# Transmitter.net
KiCad netlist of a schematic drawn in EAGLE
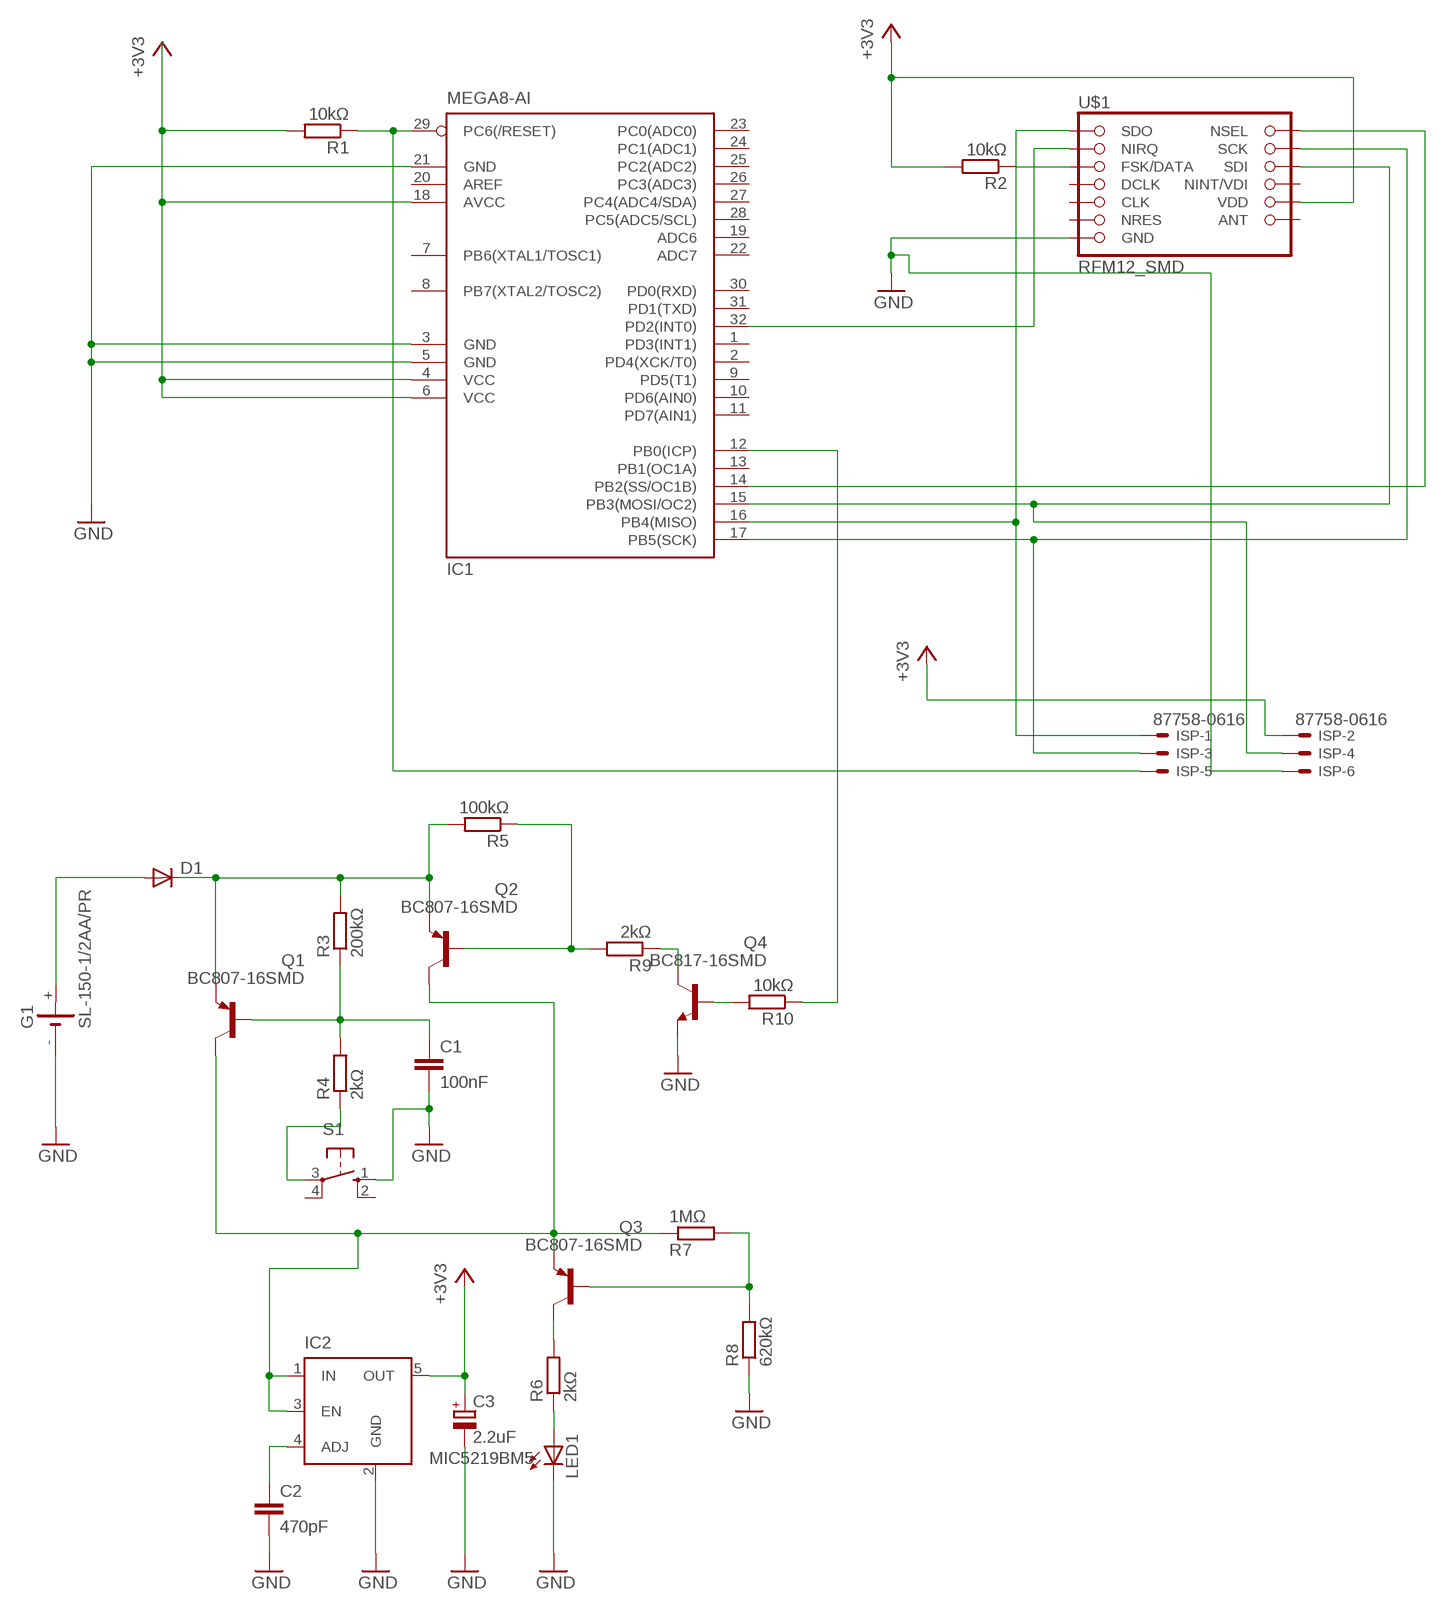
[diagram p0: schematic, sheet 1]

(export (version "E")
  (design (tool "Eeschema 10.0.6"))
  (components
    (comp (ref "C1")
      (value "100nF")
      (footprint "eagle-import:C0603")
      (libsource (lib "eagle-import") (part "C-EUC0603"))
    )
    (comp (ref "C2")
      (value "470pF")
      (footprint "eagle-import:C0603")
      (libsource (lib "eagle-import") (part "C-EUC0603"))
    )
    (comp (ref "C3")
      (value "2.2uF")
      (footprint "eagle-import:SMC_A")
      (libsource (lib "eagle-import") (part "CPOL-EUSMCA"))
    )
    (comp (ref "D1")
      (value "DIODE-SOD80C")
      (footprint "eagle-import:SOD80C")
      (libsource (lib "eagle-import") (part "DIODE-SOD80C"))
    )
    (comp (ref "G1")
      (value "SL-150-1/2AA/PR")
      (footprint "eagle-import:SL-150-1_2AA_PR")
      (libsource (lib "eagle-import") (part "SL-150-1/2AA/PR"))
    )
    (comp (ref "IC1")
      (value "MEGA8-AI")
      (footprint "eagle-import:TQFP32-08")
      (fields (field (name "MPN") "ATMEGA8-16AU"))
      (libsource (lib "eagle-import") (part "MEGA8-AI"))
    )
    (comp (ref "IC2")
      (value "MIC5219BM5")
      (footprint "eagle-import:SOT23-5")
      (fields (field (name "MF") "ALTERA CORPORATION") (field (name "MPN") "MIC5219BM5 TR"))
      (libsource (lib "eagle-import") (part "MIC5219BM5"))
    )
    (comp (ref "ISP")
      (value "87758-0616")
      (footprint "eagle-import:87758-0616")
      (libsource (lib "eagle-import") (part "87758-0616"))
    )
    (comp (ref "LED1")
      (value "LED3MM")
      (footprint "eagle-import:LED3MM")
      (libsource (lib "eagle-import") (part "LED3MM"))
    )
    (comp (ref "Q1")
      (value "BC807-16SMD")
      (footprint "eagle-import:SOT23-BEC")
      (libsource (lib "eagle-import") (part "BC807SMD-16"))
    )
    (comp (ref "Q2")
      (value "BC807-16SMD")
      (footprint "eagle-import:SOT23-BEC")
      (libsource (lib "eagle-import") (part "BC807SMD-16"))
    )
    (comp (ref "Q3")
      (value "BC807-16SMD")
      (footprint "eagle-import:SOT23-BEC")
      (libsource (lib "eagle-import") (part "BC807SMD-16"))
    )
    (comp (ref "Q4")
      (value "BC817-16SMD")
      (footprint "eagle-import:SOT23-BEC")
      (libsource (lib "eagle-import") (part "BC817SMD-16"))
    )
    (comp (ref "R1")
      (value "10kΩ")
      (footprint "eagle-import:R0603")
      (libsource (lib "eagle-import") (part "R-EU_R0603"))
    )
    (comp (ref "R2")
      (value "10kΩ")
      (footprint "eagle-import:R0603")
      (libsource (lib "eagle-import") (part "R-EU_R0603"))
    )
    (comp (ref "R3")
      (value "200kΩ")
      (footprint "eagle-import:R0603")
      (libsource (lib "eagle-import") (part "R-EU_R0603"))
    )
    (comp (ref "R4")
      (value "2kΩ")
      (footprint "eagle-import:R0603")
      (libsource (lib "eagle-import") (part "R-EU_R0603"))
    )
    (comp (ref "R5")
      (value "100kΩ")
      (footprint "eagle-import:R0603")
      (libsource (lib "eagle-import") (part "R-EU_R0603"))
    )
    (comp (ref "R6")
      (value "2kΩ")
      (footprint "eagle-import:R0603")
      (libsource (lib "eagle-import") (part "R-EU_R0603"))
    )
    (comp (ref "R7")
      (value "1MΩ")
      (footprint "eagle-import:R0603")
      (libsource (lib "eagle-import") (part "R-EU_R0603"))
    )
    (comp (ref "R8")
      (value "620kΩ")
      (footprint "eagle-import:R0603")
      (libsource (lib "eagle-import") (part "R-EU_R0603"))
    )
    (comp (ref "R9")
      (value "2kΩ")
      (footprint "eagle-import:R0603")
      (libsource (lib "eagle-import") (part "R-EU_R0603"))
    )
    (comp (ref "R10")
      (value "10kΩ")
      (footprint "eagle-import:R0603")
      (libsource (lib "eagle-import") (part "R-EU_R0603"))
    )
    (comp (ref "S1")
      (value "10-XX")
      (footprint "eagle-import:B3F-10XX")
      (fields (field (name "MPN") "B3F-1000"))
      (libsource (lib "eagle-import") (part "10-XX"))
    )
    (comp (ref "U$1")
      (value "RFM12_SMD")
      (footprint "eagle-import:RFM12_SMD")
      (libsource (lib "eagle-import") (part "RFM12_SMD"))
    )
  )
  (nets
    (net (code "1") (name "+3V3") (class "Default")
      (node (ref "C3") (pin "+") (pinfunction "+_+") (pintype "passive"))
      (node (ref "IC1") (pin "18") (pinfunction "AVCC_18") (pintype "power_in"))
      (node (ref "IC1") (pin "4") (pinfunction "VCC_4") (pintype "power_in"))
      (node (ref "IC1") (pin "6") (pinfunction "VCC_6") (pintype "power_in"))
      (node (ref "IC2") (pin "5") (pinfunction "OUT_5") (pintype "output"))
      (node (ref "ISP") (pin "2") (pinfunction "S_2") (pintype "passive"))
      (node (ref "R1") (pin "2") (pinfunction "2_2") (pintype "passive"))
      (node (ref "R2") (pin "2") (pinfunction "2_2") (pintype "passive"))
      (node (ref "U$1") (pin "9") (pinfunction "VDD_9") (pintype "power_in"))
    )
    (net (code "2") (name "GND") (class "Default")
      (node (ref "C1") (pin "2") (pinfunction "2_2") (pintype "passive"))
      (node (ref "C2") (pin "2") (pinfunction "2_2") (pintype "passive"))
      (node (ref "C3") (pin "-") (pinfunction "-_-") (pintype "passive"))
      (node (ref "G1") (pin "-") (pinfunction "-_-") (pintype "passive"))
      (node (ref "IC1") (pin "21") (pinfunction "GND_21") (pintype "power_in"))
      (node (ref "IC1") (pin "3") (pinfunction "GND_3") (pintype "power_in"))
      (node (ref "IC1") (pin "5") (pinfunction "GND_5") (pintype "power_in"))
      (node (ref "IC2") (pin "2") (pinfunction "GND_2") (pintype "power_in"))
      (node (ref "ISP") (pin "6") (pinfunction "S_6") (pintype "passive"))
      (node (ref "LED1") (pin "K") (pinfunction "C_K") (pintype "passive"))
      (node (ref "Q4") (pin "E") (pinfunction "E_E") (pintype "passive"))
      (node (ref "R8") (pin "1") (pinfunction "1_1") (pintype "passive"))
      (node (ref "S1") (pin "1") (pinfunction "S_1") (pintype "passive"))
      (node (ref "U$1") (pin "10") (pinfunction "GND_10") (pintype "power_in"))
      (node (ref "U$1") (pin "7") (pinfunction "GND_7") (pintype "power_in"))
    )
    (net (code "3") (name "Net-(C1-Pad1)") (class "Default")
      (node (ref "C1") (pin "1") (pinfunction "1_1") (pintype "passive"))
      (node (ref "Q1") (pin "B") (pinfunction "B_B") (pintype "passive"))
      (node (ref "R3") (pin "1") (pinfunction "1_1") (pintype "passive"))
      (node (ref "R4") (pin "2") (pinfunction "2_2") (pintype "passive"))
    )
    (net (code "4") (name "Net-(D1-PadA)") (class "Default")
      (node (ref "D1") (pin "A") (pinfunction "A_A") (pintype "passive"))
      (node (ref "G1") (pin "+") (pinfunction "+_+") (pintype "passive"))
    )
    (net (code "5") (name "Net-(D1-PadC)") (class "Default")
      (node (ref "D1") (pin "C") (pinfunction "C_C") (pintype "passive"))
      (node (ref "Q1") (pin "E") (pinfunction "E_E") (pintype "passive"))
      (node (ref "Q2") (pin "E") (pinfunction "E_E") (pintype "passive"))
      (node (ref "R3") (pin "2") (pinfunction "2_2") (pintype "passive"))
      (node (ref "R5") (pin "2") (pinfunction "2_2") (pintype "passive"))
    )
    (net (code "6") (name "Net-(IC1-PB0(ICP))") (class "Default")
      (node (ref "IC1") (pin "12") (pinfunction "PB0(ICP)_12") (pintype "bidirectional"))
      (node (ref "R10") (pin "1") (pinfunction "1_1") (pintype "passive"))
    )
    (net (code "7") (name "Net-(IC1-PB2(SS{slash}OC1B))") (class "Default")
      (node (ref "IC1") (pin "14") (pinfunction "PB2(SS/OC1B)_14") (pintype "bidirectional"))
      (node (ref "U$1") (pin "14") (pinfunction "NSEL_14") (pintype "input"))
    )
    (net (code "8") (name "Net-(IC1-PB3(MOSI{slash}OC2))") (class "Default")
      (node (ref "IC1") (pin "15") (pinfunction "PB3(MOSI/OC2)_15") (pintype "bidirectional"))
      (node (ref "ISP") (pin "4") (pinfunction "S_4") (pintype "passive"))
      (node (ref "U$1") (pin "12") (pinfunction "SDI_12") (pintype "input"))
    )
    (net (code "9") (name "Net-(IC1-PB4(MISO))") (class "Default")
      (node (ref "IC1") (pin "16") (pinfunction "PB4(MISO)_16") (pintype "bidirectional"))
      (node (ref "ISP") (pin "1") (pinfunction "S_1") (pintype "passive"))
      (node (ref "U$1") (pin "1") (pinfunction "SDO_1") (pintype "output"))
    )
    (net (code "10") (name "Net-(IC1-PB5(SCK))") (class "Default")
      (node (ref "IC1") (pin "17") (pinfunction "PB5(SCK)_17") (pintype "bidirectional"))
      (node (ref "ISP") (pin "3") (pinfunction "S_3") (pintype "passive"))
      (node (ref "U$1") (pin "13") (pinfunction "SCK_13") (pintype "input"))
    )
    (net (code "11") (name "Net-(IC1-PC6({slash}RESET))") (class "Default")
      (node (ref "IC1") (pin "29") (pinfunction "PC6(/RESET)_29") (pintype "bidirectional"))
      (node (ref "ISP") (pin "5") (pinfunction "S_5") (pintype "passive"))
      (node (ref "R1") (pin "1") (pinfunction "1_1") (pintype "passive"))
    )
    (net (code "12") (name "Net-(IC1-PD2(INT0))") (class "Default")
      (node (ref "IC1") (pin "32") (pinfunction "PD2(INT0)_32") (pintype "bidirectional"))
      (node (ref "U$1") (pin "2") (pinfunction "NIRQ_2") (pintype "output"))
    )
    (net (code "13") (name "Net-(IC2-ADJ)") (class "Default")
      (node (ref "C2") (pin "1") (pinfunction "1_1") (pintype "passive"))
      (node (ref "IC2") (pin "4") (pinfunction "ADJ_4") (pintype "passive"))
    )
    (net (code "14") (name "Net-(IC2-EN)") (class "Default")
      (node (ref "IC2") (pin "1") (pinfunction "IN_1") (pintype "input"))
      (node (ref "IC2") (pin "3") (pinfunction "EN_3") (pintype "input"))
      (node (ref "Q1") (pin "C") (pinfunction "C_C") (pintype "passive"))
      (node (ref "Q2") (pin "C") (pinfunction "C_C") (pintype "passive"))
      (node (ref "Q3") (pin "E") (pinfunction "E_E") (pintype "passive"))
      (node (ref "R7") (pin "1") (pinfunction "1_1") (pintype "passive"))
    )
    (net (code "15") (name "Net-(LED1-PadA)") (class "Default")
      (node (ref "LED1") (pin "A") (pinfunction "A_A") (pintype "passive"))
      (node (ref "R6") (pin "1") (pinfunction "1_1") (pintype "passive"))
    )
    (net (code "16") (name "Net-(Q2-PadB)") (class "Default")
      (node (ref "Q2") (pin "B") (pinfunction "B_B") (pintype "passive"))
      (node (ref "R5") (pin "1") (pinfunction "1_1") (pintype "passive"))
      (node (ref "R9") (pin "2") (pinfunction "2_2") (pintype "passive"))
    )
    (net (code "17") (name "Net-(Q3-PadB)") (class "Default")
      (node (ref "Q3") (pin "B") (pinfunction "B_B") (pintype "passive"))
      (node (ref "R7") (pin "2") (pinfunction "2_2") (pintype "passive"))
      (node (ref "R8") (pin "2") (pinfunction "2_2") (pintype "passive"))
    )
    (net (code "18") (name "Net-(Q3-PadC)") (class "Default")
      (node (ref "Q3") (pin "C") (pinfunction "C_C") (pintype "passive"))
      (node (ref "R6") (pin "2") (pinfunction "2_2") (pintype "passive"))
    )
    (net (code "19") (name "Net-(Q4-PadB)") (class "Default")
      (node (ref "Q4") (pin "B") (pinfunction "B_B") (pintype "passive"))
      (node (ref "R10") (pin "2") (pinfunction "2_2") (pintype "passive"))
    )
    (net (code "20") (name "Net-(Q4-PadC)") (class "Default")
      (node (ref "Q4") (pin "C") (pinfunction "C_C") (pintype "passive"))
      (node (ref "R9") (pin "1") (pinfunction "1_1") (pintype "passive"))
    )
    (net (code "21") (name "Net-(S1-P)") (class "Default")
      (node (ref "R4") (pin "1") (pinfunction "1_1") (pintype "passive"))
      (node (ref "S1") (pin "3") (pinfunction "P_3") (pintype "passive"))
    )
    (net (code "22") (name "Net-(U$1-FSK{slash}DATA)") (class "Default")
      (node (ref "R2") (pin "1") (pinfunction "1_1") (pintype "passive"))
      (node (ref "U$1") (pin "3") (pinfunction "FSK/DATA_3") (pintype "bidirectional"))
    )
    (net (code "23") (name "unconnected-(IC1-ADC6-Pad19)") (class "Default")
      (node (ref "IC1") (pin "19") (pinfunction "ADC6_19") (pintype "bidirectional"))
    )
    (net (code "24") (name "unconnected-(IC1-ADC7-Pad22)") (class "Default")
      (node (ref "IC1") (pin "22") (pinfunction "ADC7_22") (pintype "bidirectional"))
    )
    (net (code "25") (name "unconnected-(IC1-AREF-Pad20)") (class "Default")
      (node (ref "IC1") (pin "20") (pinfunction "AREF_20") (pintype "passive"))
    )
    (net (code "26") (name "unconnected-(IC1-PB1(OC1A)-Pad13)") (class "Default")
      (node (ref "IC1") (pin "13") (pinfunction "PB1(OC1A)_13") (pintype "bidirectional"))
    )
    (net (code "27") (name "unconnected-(IC1-PB6(XTAL1{slash}TOSC1)-Pad7)") (class "Default")
      (node (ref "IC1") (pin "7") (pinfunction "PB6(XTAL1/TOSC1)_7") (pintype "bidirectional"))
    )
    (net (code "28") (name "unconnected-(IC1-PB7(XTAL2{slash}TOSC2)-Pad8)") (class "Default")
      (node (ref "IC1") (pin "8") (pinfunction "PB7(XTAL2/TOSC2)_8") (pintype "bidirectional"))
    )
    (net (code "29") (name "unconnected-(IC1-PC0(ADC0)-Pad23)") (class "Default")
      (node (ref "IC1") (pin "23") (pinfunction "PC0(ADC0)_23") (pintype "bidirectional"))
    )
    (net (code "30") (name "unconnected-(IC1-PC1(ADC1)-Pad24)") (class "Default")
      (node (ref "IC1") (pin "24") (pinfunction "PC1(ADC1)_24") (pintype "bidirectional"))
    )
    (net (code "31") (name "unconnected-(IC1-PC2(ADC2)-Pad25)") (class "Default")
      (node (ref "IC1") (pin "25") (pinfunction "PC2(ADC2)_25") (pintype "bidirectional"))
    )
    (net (code "32") (name "unconnected-(IC1-PC3(ADC3)-Pad26)") (class "Default")
      (node (ref "IC1") (pin "26") (pinfunction "PC3(ADC3)_26") (pintype "bidirectional"))
    )
    (net (code "33") (name "unconnected-(IC1-PC4(ADC4{slash}SDA)-Pad27)") (class "Default")
      (node (ref "IC1") (pin "27") (pinfunction "PC4(ADC4/SDA)_27") (pintype "bidirectional"))
    )
    (net (code "34") (name "unconnected-(IC1-PC5(ADC5{slash}SCL)-Pad28)") (class "Default")
      (node (ref "IC1") (pin "28") (pinfunction "PC5(ADC5/SCL)_28") (pintype "bidirectional"))
    )
    (net (code "35") (name "unconnected-(IC1-PD0(RXD)-Pad30)") (class "Default")
      (node (ref "IC1") (pin "30") (pinfunction "PD0(RXD)_30") (pintype "bidirectional"))
    )
    (net (code "36") (name "unconnected-(IC1-PD1(TXD)-Pad31)") (class "Default")
      (node (ref "IC1") (pin "31") (pinfunction "PD1(TXD)_31") (pintype "bidirectional"))
    )
    (net (code "37") (name "unconnected-(IC1-PD3(INT1)-Pad1)") (class "Default")
      (node (ref "IC1") (pin "1") (pinfunction "PD3(INT1)_1") (pintype "bidirectional"))
    )
    (net (code "38") (name "unconnected-(IC1-PD4(XCK{slash}T0)-Pad2)") (class "Default")
      (node (ref "IC1") (pin "2") (pinfunction "PD4(XCK/T0)_2") (pintype "bidirectional"))
    )
    (net (code "39") (name "unconnected-(IC1-PD5(T1)-Pad9)") (class "Default")
      (node (ref "IC1") (pin "9") (pinfunction "PD5(T1)_9") (pintype "bidirectional"))
    )
    (net (code "40") (name "unconnected-(IC1-PD6(AIN0)-Pad10)") (class "Default")
      (node (ref "IC1") (pin "10") (pinfunction "PD6(AIN0)_10") (pintype "bidirectional"))
    )
    (net (code "41") (name "unconnected-(IC1-PD7(AIN1)-Pad11)") (class "Default")
      (node (ref "IC1") (pin "11") (pinfunction "PD7(AIN1)_11") (pintype "bidirectional"))
    )
    (net (code "42") (name "unconnected-(S1-P1-Pad4)") (class "Default")
      (node (ref "S1") (pin "4") (pinfunction "P1_4") (pintype "passive"))
    )
    (net (code "43") (name "unconnected-(S1-S1-Pad2)") (class "Default")
      (node (ref "S1") (pin "2") (pinfunction "S1_2") (pintype "passive"))
    )
    (net (code "44") (name "unconnected-(U$1-ANT-Pad8)") (class "Default")
      (node (ref "U$1") (pin "8") (pinfunction "ANT_8") (pintype "output"))
    )
    (net (code "45") (name "unconnected-(U$1-CLK-Pad5)") (class "Default")
      (node (ref "U$1") (pin "5") (pinfunction "CLK_5") (pintype "output"))
    )
    (net (code "46") (name "unconnected-(U$1-DCLK-Pad4)") (class "Default")
      (node (ref "U$1") (pin "4") (pinfunction "DCLK_4") (pintype "bidirectional"))
    )
    (net (code "47") (name "unconnected-(U$1-NINT{slash}VDI-Pad11)") (class "Default")
      (node (ref "U$1") (pin "11") (pinfunction "NINT/VDI_11") (pintype "bidirectional"))
    )
    (net (code "48") (name "unconnected-(U$1-NRES-Pad6)") (class "Default")
      (node (ref "U$1") (pin "6") (pinfunction "NRES_6") (pintype "bidirectional"))
    )
  )
)
